# squawkbox_m_0_1.net
KiCad netlist of a schematic drawn in EAGLE
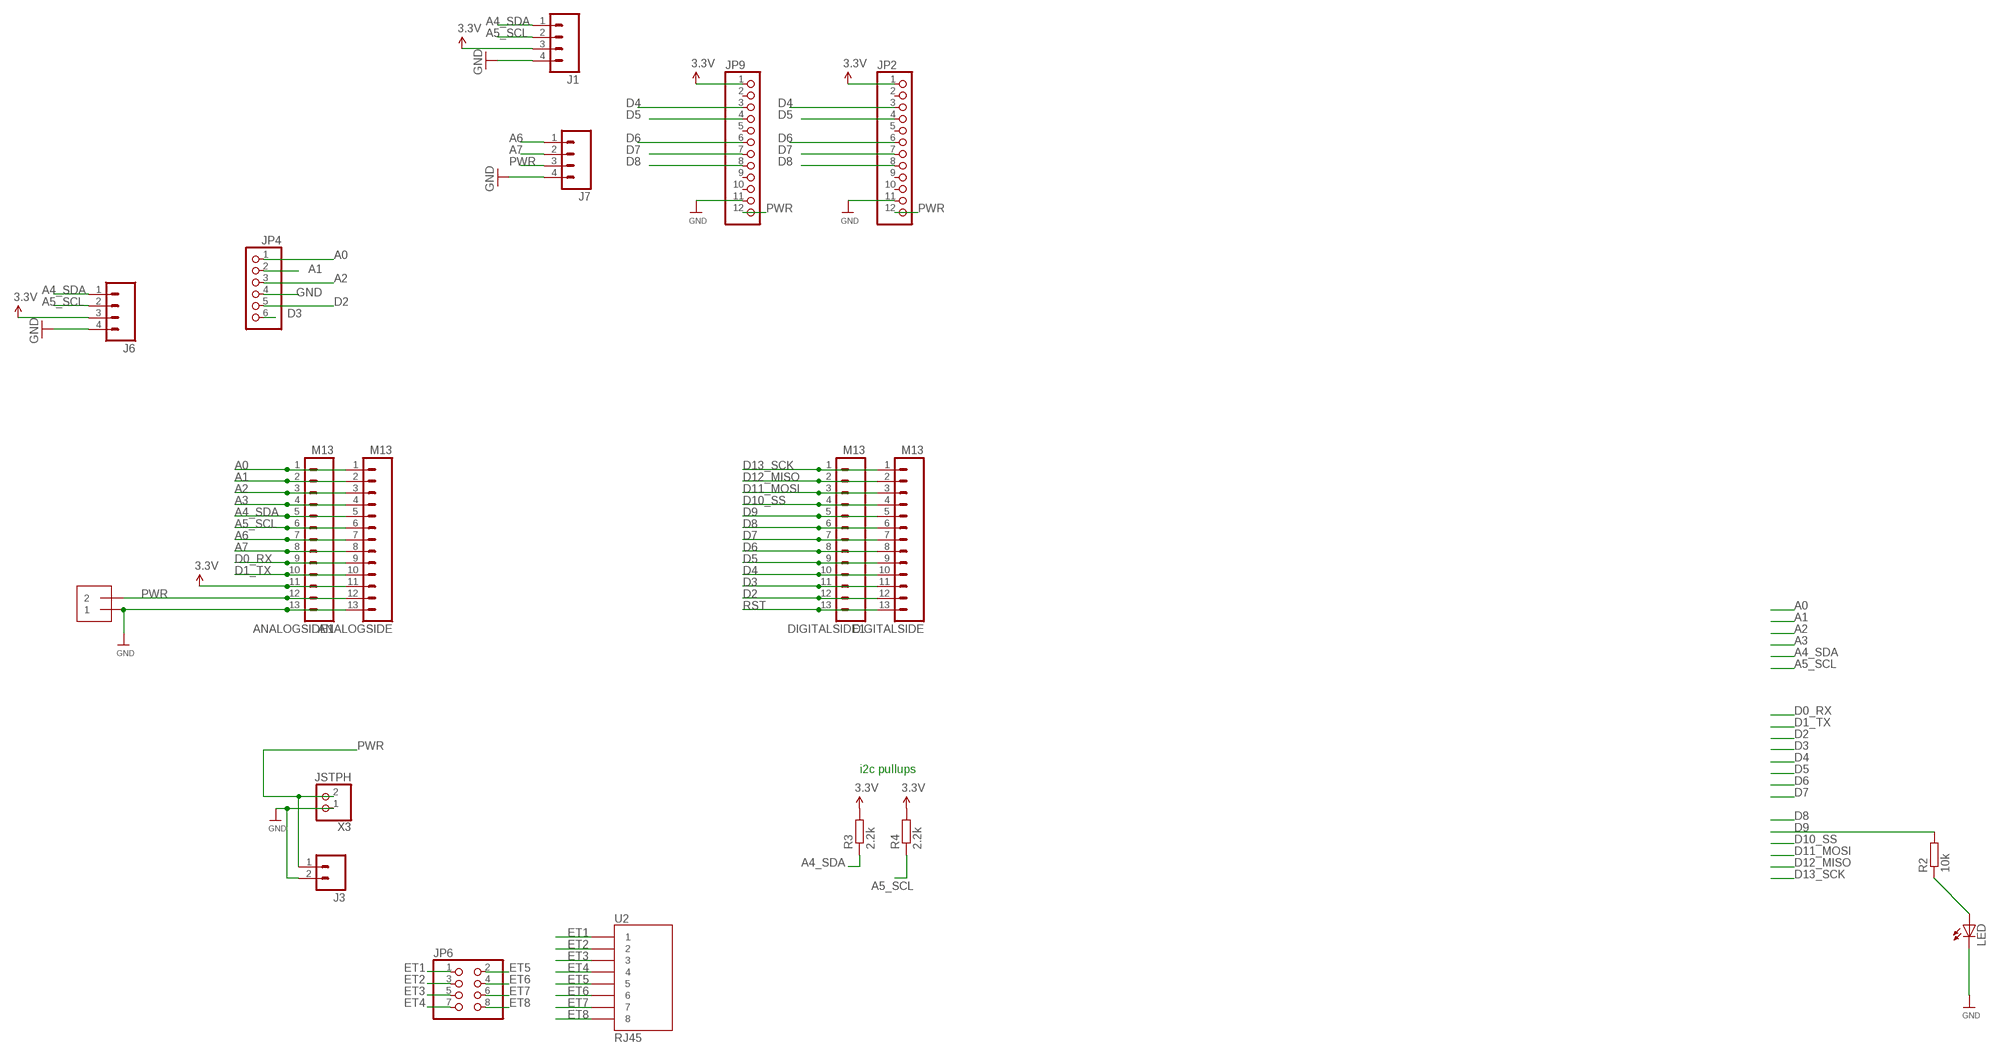
[diagram p0: schematic, sheet 1]

(export (version "E")
  (design (tool "Eeschema 10.0.6"))
  (components
    (comp (ref "ANALOGSIDE")
      (value "M13")
      (footprint "eagle-import:1X13")
      (libsource (lib "eagle-import") (part "M13"))
    )
    (comp (ref "ANALOGSIDE1")
      (value "M13")
      (footprint "eagle-import:1X13")
      (libsource (lib "eagle-import") (part "M13"))
    )
    (comp (ref "DIGITALSIDE")
      (value "M13")
      (footprint "eagle-import:1X13")
      (libsource (lib "eagle-import") (part "M13"))
    )
    (comp (ref "DIGITALSIDE1")
      (value "M13")
      (footprint "eagle-import:1X13")
      (libsource (lib "eagle-import") (part "M13"))
    )
    (comp (ref "J1")
      (value "M04PTH")
      (footprint "eagle-import:1X04")
      (libsource (lib "eagle-import") (part "M04PTH"))
    )
    (comp (ref "J2")
      (value "1X2-3.5MM")
      (footprint "eagle-import:1X2-3.5MM")
      (libsource (lib "eagle-import") (part "1X2-3.5MM"))
    )
    (comp (ref "J3")
      (value "M02PTH")
      (footprint "eagle-import:1X02")
      (libsource (lib "eagle-import") (part "M02PTH"))
    )
    (comp (ref "J6")
      (value "M04SCREW")
      (footprint "eagle-import:SCREWTERMINAL-3.5MM-4")
      (libsource (lib "eagle-import") (part "M04SCREW"))
    )
    (comp (ref "J7")
      (value "M04SCREW")
      (footprint "eagle-import:SCREWTERMINAL-3.5MM-4")
      (libsource (lib "eagle-import") (part "M04SCREW"))
    )
    (comp (ref "JP2")
      (value "PINHD-1X12-CB")
      (footprint "eagle-import:1X12-CB")
      (libsource (lib "eagle-import") (part "PINHD-1X12-CB"))
    )
    (comp (ref "JP4")
      (value "PINHD-1X6-3.5MM")
      (footprint "eagle-import:1X06-3.5MM")
      (libsource (lib "eagle-import") (part "PINHD-1X6-3.5MM"))
    )
    (comp (ref "JP6")
      (value "PINHD-2X4")
      (footprint "eagle-import:2X04")
      (libsource (lib "eagle-import") (part "PINHD-2X4"))
    )
    (comp (ref "JP9")
      (value "PINHD-1X12-CB")
      (footprint "eagle-import:1X12-CB")
      (libsource (lib "eagle-import") (part "PINHD-1X12-CB"))
    )
    (comp (ref "LED")
      (value "LED3MM")
      (footprint "eagle-import:LED3MM")
      (libsource (lib "eagle-import") (part "LED3MM"))
    )
    (comp (ref "R2")
      (value "10k")
      (footprint "eagle-import:0204_7")
      (libsource (lib "eagle-import") (part "R-EU_0204/7"))
    )
    (comp (ref "R3")
      (value "2.2k")
      (footprint "eagle-import:0204_7")
      (libsource (lib "eagle-import") (part "R-EU_0204/7"))
    )
    (comp (ref "R4")
      (value "2.2k")
      (footprint "eagle-import:0204_7")
      (libsource (lib "eagle-import") (part "R-EU_0204/7"))
    )
    (comp (ref "U2")
      (value "RJ45")
      (footprint "eagle-import:RJ45-8")
      (libsource (lib "eagle-import") (part "RJ45-8PTH"))
    )
    (comp (ref "X3")
      (value "JSTPH")
      (footprint "eagle-import:JSTPH2")
      (libsource (lib "eagle-import") (part "CON_JST_PH_2PIN"))
    )
  )
  (nets
    (net (code "1") (name "/A0") (class "Default")
      (node (ref "ANALOGSIDE") (pin "1") (pinfunction "1_1") (pintype "passive"))
      (node (ref "ANALOGSIDE1") (pin "1") (pinfunction "1_1") (pintype "passive"))
      (node (ref "JP4") (pin "1") (pinfunction "1_1") (pintype "passive"))
    )
    (net (code "2") (name "/A1") (class "Default")
      (node (ref "ANALOGSIDE") (pin "2") (pinfunction "2_2") (pintype "passive"))
      (node (ref "ANALOGSIDE1") (pin "2") (pinfunction "2_2") (pintype "passive"))
      (node (ref "JP4") (pin "2") (pinfunction "2_2") (pintype "passive"))
    )
    (net (code "3") (name "/A2") (class "Default")
      (node (ref "ANALOGSIDE") (pin "3") (pinfunction "3_3") (pintype "passive"))
      (node (ref "ANALOGSIDE1") (pin "3") (pinfunction "3_3") (pintype "passive"))
      (node (ref "JP4") (pin "3") (pinfunction "3_3") (pintype "passive"))
    )
    (net (code "4") (name "/A3") (class "Default")
      (node (ref "ANALOGSIDE") (pin "4") (pinfunction "4_4") (pintype "passive"))
      (node (ref "ANALOGSIDE1") (pin "4") (pinfunction "4_4") (pintype "passive"))
    )
    (net (code "5") (name "/A4_SDA") (class "Default")
      (node (ref "ANALOGSIDE") (pin "5") (pinfunction "5_5") (pintype "passive"))
      (node (ref "ANALOGSIDE1") (pin "5") (pinfunction "5_5") (pintype "passive"))
      (node (ref "J1") (pin "1") (pinfunction "1_1") (pintype "passive"))
      (node (ref "J6") (pin "1") (pinfunction "1_1") (pintype "passive"))
      (node (ref "R3") (pin "1") (pinfunction "1_1") (pintype "passive"))
    )
    (net (code "6") (name "/A5_SCL") (class "Default")
      (node (ref "ANALOGSIDE") (pin "6") (pinfunction "6_6") (pintype "passive"))
      (node (ref "ANALOGSIDE1") (pin "6") (pinfunction "6_6") (pintype "passive"))
      (node (ref "J1") (pin "2") (pinfunction "2_2") (pintype "passive"))
      (node (ref "J6") (pin "2") (pinfunction "2_2") (pintype "passive"))
      (node (ref "R4") (pin "1") (pinfunction "1_1") (pintype "passive"))
    )
    (net (code "7") (name "/A6") (class "Default")
      (node (ref "ANALOGSIDE") (pin "7") (pinfunction "7_7") (pintype "passive"))
      (node (ref "ANALOGSIDE1") (pin "7") (pinfunction "7_7") (pintype "passive"))
      (node (ref "J7") (pin "1") (pinfunction "1_1") (pintype "passive"))
    )
    (net (code "8") (name "/A7") (class "Default")
      (node (ref "ANALOGSIDE") (pin "8") (pinfunction "8_8") (pintype "passive"))
      (node (ref "ANALOGSIDE1") (pin "8") (pinfunction "8_8") (pintype "passive"))
      (node (ref "J7") (pin "2") (pinfunction "2_2") (pintype "passive"))
    )
    (net (code "9") (name "/D0_RX") (class "Default")
      (node (ref "ANALOGSIDE") (pin "9") (pinfunction "9_9") (pintype "passive"))
      (node (ref "ANALOGSIDE1") (pin "9") (pinfunction "9_9") (pintype "passive"))
    )
    (net (code "10") (name "/D1_TX") (class "Default")
      (node (ref "ANALOGSIDE") (pin "10") (pinfunction "10_10") (pintype "passive"))
      (node (ref "ANALOGSIDE1") (pin "10") (pinfunction "10_10") (pintype "passive"))
    )
    (net (code "11") (name "/D2") (class "Default")
      (node (ref "DIGITALSIDE") (pin "12") (pinfunction "12_12") (pintype "passive"))
      (node (ref "DIGITALSIDE1") (pin "12") (pinfunction "12_12") (pintype "passive"))
      (node (ref "JP4") (pin "5") (pinfunction "5_5") (pintype "passive"))
    )
    (net (code "12") (name "/D3") (class "Default")
      (node (ref "DIGITALSIDE") (pin "11") (pinfunction "11_11") (pintype "passive"))
      (node (ref "DIGITALSIDE1") (pin "11") (pinfunction "11_11") (pintype "passive"))
      (node (ref "JP4") (pin "6") (pinfunction "6_6") (pintype "passive"))
    )
    (net (code "13") (name "/D4") (class "Default")
      (node (ref "DIGITALSIDE") (pin "10") (pinfunction "10_10") (pintype "passive"))
      (node (ref "DIGITALSIDE1") (pin "10") (pinfunction "10_10") (pintype "passive"))
      (node (ref "JP2") (pin "3") (pinfunction "3_3") (pintype "passive"))
      (node (ref "JP9") (pin "3") (pinfunction "3_3") (pintype "passive"))
    )
    (net (code "14") (name "/D5") (class "Default")
      (node (ref "DIGITALSIDE") (pin "9") (pinfunction "9_9") (pintype "passive"))
      (node (ref "DIGITALSIDE1") (pin "9") (pinfunction "9_9") (pintype "passive"))
      (node (ref "JP2") (pin "4") (pinfunction "4_4") (pintype "passive"))
      (node (ref "JP9") (pin "4") (pinfunction "4_4") (pintype "passive"))
    )
    (net (code "15") (name "/D6") (class "Default")
      (node (ref "DIGITALSIDE") (pin "8") (pinfunction "8_8") (pintype "passive"))
      (node (ref "DIGITALSIDE1") (pin "8") (pinfunction "8_8") (pintype "passive"))
      (node (ref "JP2") (pin "6") (pinfunction "6_6") (pintype "passive"))
      (node (ref "JP9") (pin "6") (pinfunction "6_6") (pintype "passive"))
    )
    (net (code "16") (name "/D7") (class "Default")
      (node (ref "DIGITALSIDE") (pin "7") (pinfunction "7_7") (pintype "passive"))
      (node (ref "DIGITALSIDE1") (pin "7") (pinfunction "7_7") (pintype "passive"))
      (node (ref "JP2") (pin "7") (pinfunction "7_7") (pintype "passive"))
      (node (ref "JP9") (pin "7") (pinfunction "7_7") (pintype "passive"))
    )
    (net (code "17") (name "/D8") (class "Default")
      (node (ref "DIGITALSIDE") (pin "6") (pinfunction "6_6") (pintype "passive"))
      (node (ref "DIGITALSIDE1") (pin "6") (pinfunction "6_6") (pintype "passive"))
      (node (ref "JP2") (pin "8") (pinfunction "8_8") (pintype "passive"))
      (node (ref "JP9") (pin "8") (pinfunction "8_8") (pintype "passive"))
    )
    (net (code "18") (name "/D9") (class "Default")
      (node (ref "DIGITALSIDE") (pin "5") (pinfunction "5_5") (pintype "passive"))
      (node (ref "DIGITALSIDE1") (pin "5") (pinfunction "5_5") (pintype "passive"))
      (node (ref "R2") (pin "2") (pinfunction "2_2") (pintype "passive"))
    )
    (net (code "19") (name "/D10_SS") (class "Default")
      (node (ref "DIGITALSIDE") (pin "4") (pinfunction "4_4") (pintype "passive"))
      (node (ref "DIGITALSIDE1") (pin "4") (pinfunction "4_4") (pintype "passive"))
    )
    (net (code "20") (name "/D11_MOSI") (class "Default")
      (node (ref "DIGITALSIDE") (pin "3") (pinfunction "3_3") (pintype "passive"))
      (node (ref "DIGITALSIDE1") (pin "3") (pinfunction "3_3") (pintype "passive"))
    )
    (net (code "21") (name "/D12_MISO") (class "Default")
      (node (ref "DIGITALSIDE") (pin "2") (pinfunction "2_2") (pintype "passive"))
      (node (ref "DIGITALSIDE1") (pin "2") (pinfunction "2_2") (pintype "passive"))
    )
    (net (code "22") (name "/D13_SCK") (class "Default")
      (node (ref "DIGITALSIDE") (pin "1") (pinfunction "1_1") (pintype "passive"))
      (node (ref "DIGITALSIDE1") (pin "1") (pinfunction "1_1") (pintype "passive"))
    )
    (net (code "23") (name "/ET1") (class "Default")
      (node (ref "JP6") (pin "1") (pinfunction "1_1") (pintype "passive"))
      (node (ref "U2") (pin "1") (pinfunction "1_1") (pintype "bidirectional"))
    )
    (net (code "24") (name "/ET2") (class "Default")
      (node (ref "JP6") (pin "3") (pinfunction "3_3") (pintype "passive"))
      (node (ref "U2") (pin "2") (pinfunction "2_2") (pintype "bidirectional"))
    )
    (net (code "25") (name "/ET3") (class "Default")
      (node (ref "JP6") (pin "5") (pinfunction "5_5") (pintype "passive"))
      (node (ref "U2") (pin "3") (pinfunction "3_3") (pintype "bidirectional"))
    )
    (net (code "26") (name "/ET4") (class "Default")
      (node (ref "JP6") (pin "7") (pinfunction "7_7") (pintype "passive"))
      (node (ref "U2") (pin "4") (pinfunction "4_4") (pintype "bidirectional"))
    )
    (net (code "27") (name "/ET5") (class "Default")
      (node (ref "JP6") (pin "2") (pinfunction "2_2") (pintype "passive"))
      (node (ref "U2") (pin "5") (pinfunction "5_5") (pintype "bidirectional"))
    )
    (net (code "28") (name "/ET6") (class "Default")
      (node (ref "JP6") (pin "4") (pinfunction "4_4") (pintype "passive"))
      (node (ref "U2") (pin "6") (pinfunction "6_6") (pintype "bidirectional"))
    )
    (net (code "29") (name "/ET7") (class "Default")
      (node (ref "JP6") (pin "6") (pinfunction "6_6") (pintype "passive"))
      (node (ref "U2") (pin "7") (pinfunction "7_7") (pintype "bidirectional"))
    )
    (net (code "30") (name "/ET8") (class "Default")
      (node (ref "JP6") (pin "8") (pinfunction "8_8") (pintype "passive"))
      (node (ref "U2") (pin "8") (pinfunction "8_8") (pintype "bidirectional"))
    )
    (net (code "31") (name "/PWR") (class "Default")
      (node (ref "ANALOGSIDE") (pin "12") (pinfunction "12_12") (pintype "passive"))
      (node (ref "ANALOGSIDE1") (pin "12") (pinfunction "12_12") (pintype "passive"))
      (node (ref "J2") (pin "2") (pinfunction "2_2") (pintype "passive"))
      (node (ref "J3") (pin "1") (pinfunction "1_1") (pintype "passive"))
      (node (ref "J7") (pin "3") (pinfunction "3_3") (pintype "passive"))
      (node (ref "JP2") (pin "12") (pinfunction "12_12") (pintype "passive"))
      (node (ref "JP9") (pin "12") (pinfunction "12_12") (pintype "passive"))
      (node (ref "X3") (pin "2") (pinfunction "2_2") (pintype "passive"))
    )
    (net (code "32") (name "/RST") (class "Default")
      (node (ref "DIGITALSIDE") (pin "13") (pinfunction "13_13") (pintype "passive"))
      (node (ref "DIGITALSIDE1") (pin "13") (pinfunction "13_13") (pintype "passive"))
    )
    (net (code "33") (name "3.3V") (class "Default")
      (node (ref "ANALOGSIDE") (pin "11") (pinfunction "11_11") (pintype "passive"))
      (node (ref "ANALOGSIDE1") (pin "11") (pinfunction "11_11") (pintype "passive"))
      (node (ref "J1") (pin "3") (pinfunction "3_3") (pintype "passive"))
      (node (ref "J6") (pin "3") (pinfunction "3_3") (pintype "passive"))
      (node (ref "JP2") (pin "1") (pinfunction "1_1") (pintype "passive"))
      (node (ref "JP9") (pin "1") (pinfunction "1_1") (pintype "passive"))
      (node (ref "R3") (pin "2") (pinfunction "2_2") (pintype "passive"))
      (node (ref "R4") (pin "2") (pinfunction "2_2") (pintype "passive"))
    )
    (net (code "34") (name "GND") (class "Default")
      (node (ref "ANALOGSIDE") (pin "13") (pinfunction "13_13") (pintype "passive"))
      (node (ref "ANALOGSIDE1") (pin "13") (pinfunction "13_13") (pintype "passive"))
      (node (ref "J1") (pin "4") (pinfunction "4_4") (pintype "passive"))
      (node (ref "J2") (pin "1") (pinfunction "1_1") (pintype "passive"))
      (node (ref "J3") (pin "2") (pinfunction "2_2") (pintype "passive"))
      (node (ref "J6") (pin "4") (pinfunction "4_4") (pintype "passive"))
      (node (ref "J7") (pin "4") (pinfunction "4_4") (pintype "passive"))
      (node (ref "JP2") (pin "11") (pinfunction "11_11") (pintype "passive"))
      (node (ref "JP4") (pin "4") (pinfunction "4_4") (pintype "passive"))
      (node (ref "JP9") (pin "11") (pinfunction "11_11") (pintype "passive"))
      (node (ref "LED") (pin "K") (pinfunction "C_K") (pintype "passive"))
      (node (ref "X3") (pin "1") (pinfunction "1_1") (pintype "passive"))
    )
    (net (code "35") (name "Net-(LED-PadA)") (class "Default")
      (node (ref "LED") (pin "A") (pinfunction "A_A") (pintype "passive"))
      (node (ref "R2") (pin "1") (pinfunction "1_1") (pintype "passive"))
    )
    (net (code "36") (name "unconnected-(JP2-Pad2)") (class "Default")
      (node (ref "JP2") (pin "2") (pinfunction "2_2") (pintype "passive"))
    )
    (net (code "37") (name "unconnected-(JP2-Pad5)") (class "Default")
      (node (ref "JP2") (pin "5") (pinfunction "5_5") (pintype "passive"))
    )
    (net (code "38") (name "unconnected-(JP2-Pad9)") (class "Default")
      (node (ref "JP2") (pin "9") (pinfunction "9_9") (pintype "passive"))
    )
    (net (code "39") (name "unconnected-(JP2-Pad10)") (class "Default")
      (node (ref "JP2") (pin "10") (pinfunction "10_10") (pintype "passive"))
    )
    (net (code "40") (name "unconnected-(JP9-Pad2)") (class "Default")
      (node (ref "JP9") (pin "2") (pinfunction "2_2") (pintype "passive"))
    )
    (net (code "41") (name "unconnected-(JP9-Pad5)") (class "Default")
      (node (ref "JP9") (pin "5") (pinfunction "5_5") (pintype "passive"))
    )
    (net (code "42") (name "unconnected-(JP9-Pad9)") (class "Default")
      (node (ref "JP9") (pin "9") (pinfunction "9_9") (pintype "passive"))
    )
    (net (code "43") (name "unconnected-(JP9-Pad10)") (class "Default")
      (node (ref "JP9") (pin "10") (pinfunction "10_10") (pintype "passive"))
    )
  )
)
